# 4_F2838_JTAG_CLOCK_SUP.net
KiCad netlist of a schematic drawn in Altium Designer
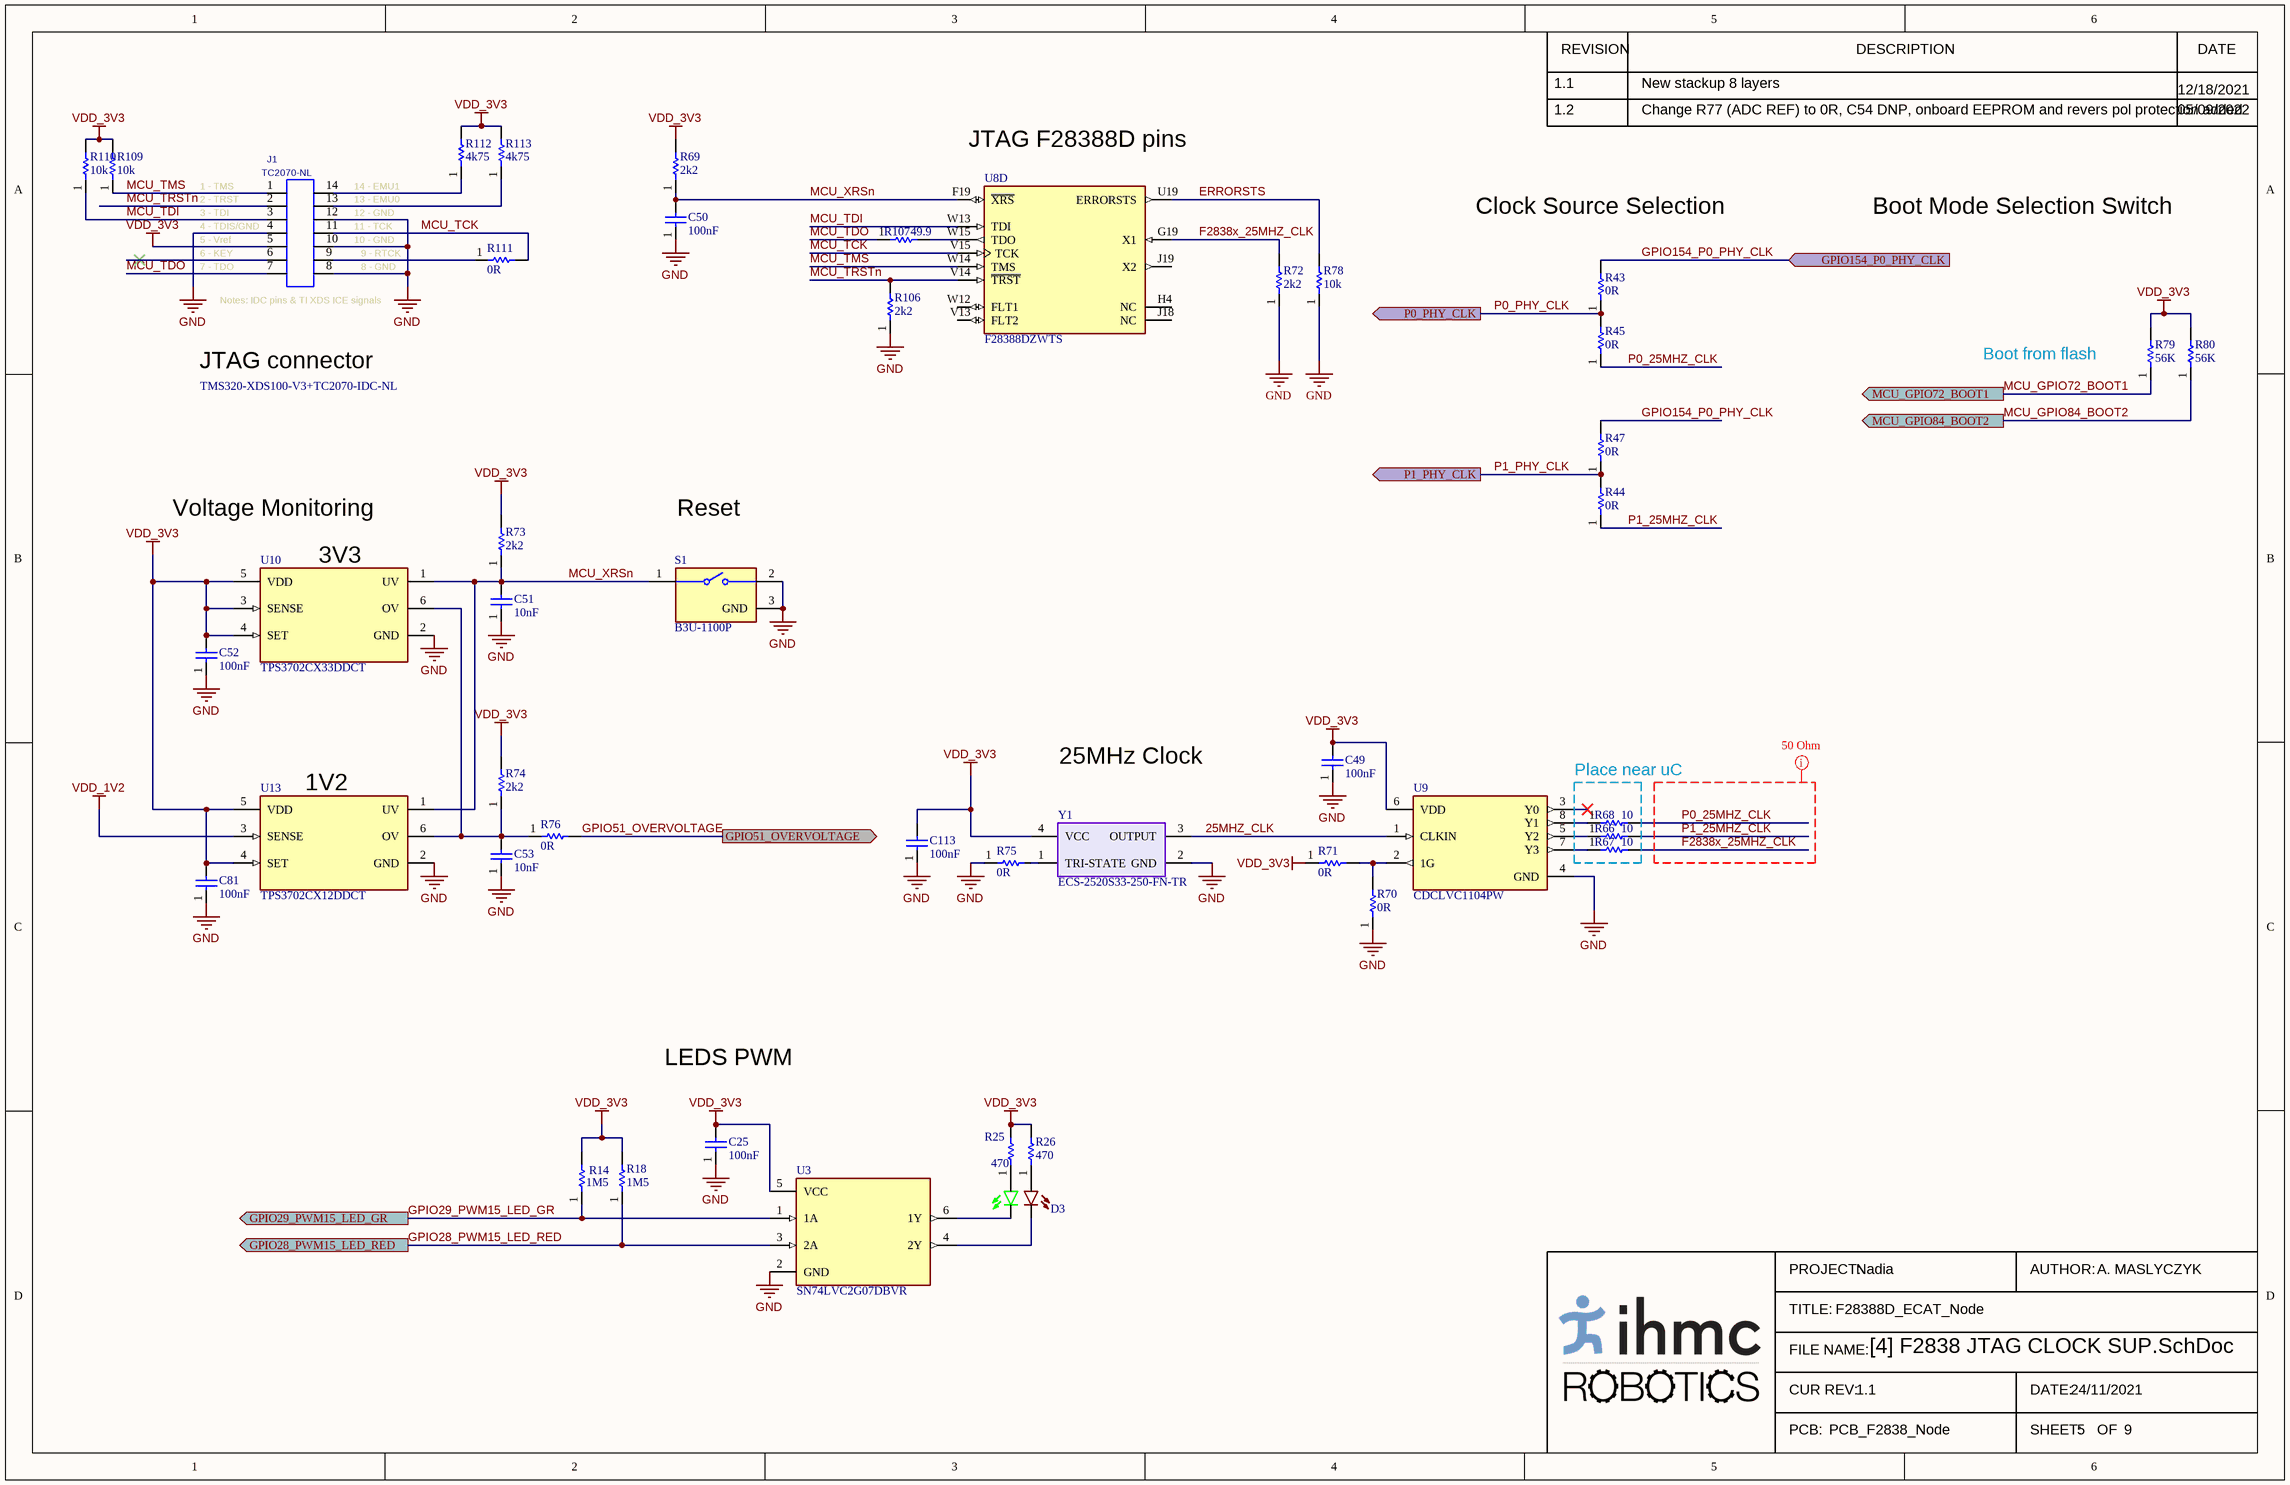
[diagram p0: [4] F2838 JTAG CLOCK SUP.SchDoc]

(export (version "E")
  (design (tool "Eeschema 10.0.6"))
  (components
    (comp (ref "C25")
      (value "100nF")
      (footprint "CAPC1005X03N(0402)")
      (description "CAP CER 0.1UF 16V X7R 0402")
      (fields (field (name "MPN") "GRM155R71C104JA88D") (field (name "TOLERANCE") "5%"))
      (libsource (lib "IHMC_Altium_Lib") (part "100nF_16V_0402_CAP"))
    )
    (comp (ref "C49")
      (value "100nF")
      (footprint "CAPC1005X03N(0402)")
      (description "CAP CER 0.1UF 16V X7R 0402")
      (fields (field (name "MPN") "GRM155R71C104JA88D") (field (name "TOLERANCE") "5%"))
      (libsource (lib "IHMC_Altium_Lib") (part "100nF_16V_0402_CAP"))
    )
    (comp (ref "C50")
      (value "100nF")
      (footprint "CAPC1005X03N(0402)")
      (description "CAP CER 0.1UF 16V X7R 0402")
      (fields (field (name "MPN") "GRM155R71C104JA88D") (field (name "TOLERANCE") "5%"))
      (libsource (lib "IHMC_Altium_Lib") (part "100nF_16V_0402_CAP"))
    )
    (comp (ref "C51")
      (value "10nF")
      (footprint "CAPC1005X03N(0402)")
      (description "CAP CER 10000PF 50V X7R 0402")
      (fields (field (name "MPN") "CC0402KRX7R9BB103") (field (name "VOLTAGE") "50V"))
      (libsource (lib "IHMC_Altium_Lib") (part "10nF_50V_0402_CAP"))
    )
    (comp (ref "C52")
      (value "100nF")
      (footprint "CAPC1005X03N(0402)")
      (description "CAP CER 0.1UF 16V X7R 0402")
      (fields (field (name "MPN") "GRM155R71C104JA88D") (field (name "TOLERANCE") "5%"))
      (libsource (lib "IHMC_Altium_Lib") (part "100nF_16V_0402_CAP"))
    )
    (comp (ref "C53")
      (value "10nF")
      (footprint "CAPC1005X03N(0402)")
      (description "CAP CER 10000PF 50V X7R 0402")
      (fields (field (name "MPN") "CC0402KRX7R9BB103") (field (name "VOLTAGE") "50V"))
      (libsource (lib "IHMC_Altium_Lib") (part "10nF_50V_0402_CAP"))
    )
    (comp (ref "C81")
      (value "100nF")
      (footprint "CAPC1608X09N(0603)")
      (description "CAP CER 0.1UF 50V X7R 0603")
      (fields (field (name "MPN") "CL10B104KB8NNNL") (field (name "TOLERANCE") "105"))
      (libsource (lib "IHMC_Altium_Lib") (part "100nF_50V_0603_CAP"))
    )
    (comp (ref "C113")
      (value "100nF")
      (footprint "CAPC1005X03N(0402)")
      (description "CAP CER 0.1UF 16V X7R 0402")
      (fields (field (name "MPN") "GRM155R71C104JA88D") (field (name "TOLERANCE") "5%"))
      (libsource (lib "IHMC_Altium_Lib") (part "100nF_16V_0402_CAP"))
    )
    (comp (ref "D3")
      (value "LTST-C195KGJRKT")
      (footprint "Dual_LED")
      (description "LED GREEN/RED CLEAR CHIP SMD")
      (libsource (lib "IHMC_Altium_Lib") (part "Green/Red_LED"))
    )
    (comp (ref "J1")
      (value "TC2070-NL")
      (footprint "TC2070-NL")
      (description "HDR, TC2070, 14 Pin, Footprint only")
      (libsource (lib "IHMC_Altium_Lib") (part "HDR 14 TC2070-NL"))
    )
    (comp (ref "R14")
      (value "1M5")
      (footprint "0402")
      (description "RES SMD 1.5M OHM 5% 1/16W 0402")
      (fields
        (field (name "MANUFACTURER") "Vishay Dale")
        (field (name "MANUFACTURER PART NUMBER") "CRCW04021M50JNED")
      )
      (libsource (lib "IHMC_Altium_Lib") (part "1M5_1/16W_0402_CRCW04021M50JNED_RES"))
    )
    (comp (ref "R18")
      (value "1M5")
      (footprint "0402")
      (description "RES SMD 1.5M OHM 5% 1/16W 0402")
      (fields
        (field (name "MANUFACTURER") "Vishay Dale")
        (field (name "MANUFACTURER PART NUMBER") "CRCW04021M50JNED")
      )
      (libsource (lib "IHMC_Altium_Lib") (part "1M5_1/16W_0402_CRCW04021M50JNED_RES"))
    )
    (comp (ref "R25")
      (value "470")
      (footprint "0402")
      (description "Vishay CRCW Series Thick Film Resistor 0402 Case 470 5% 0.063W 200ppm/K")
      (fields
        (field (name "MANUFACTURER") "Vishay Dale")
        (field (name "MANUFACTURER PART NUMBER") "CRCW0402470RJNED")
      )
      (libsource (lib "IHMC_Altium_Lib") (part "470_1/10W_0402_CRCW0402470RJNED"))
    )
    (comp (ref "R26")
      (value "470")
      (footprint "0402")
      (description "Vishay CRCW Series Thick Film Resistor 0402 Case 470 5% 0.063W 200ppm/K")
      (fields
        (field (name "MANUFACTURER") "Vishay Dale")
        (field (name "MANUFACTURER PART NUMBER") "CRCW0402470RJNED")
      )
      (libsource (lib "IHMC_Altium_Lib") (part "470_1/10W_0402_CRCW0402470RJNED"))
    )
    (comp (ref "R43")
      (value "0R")
      (footprint "0402")
      (fields
        (field (name "MANUFACTURER") "Vishay Dale")
        (field (name "MANUFACTURER PART NUMBER") "RCS04020000Z0ED")
      )
      (libsource (lib "IHMC_Altium_Lib") (part "0R_1/5W_0402_RCS04020000Z0ED_RES"))
    )
    (comp (ref "R44")
      (value "0R")
      (footprint "0402")
      (fields
        (field (name "MANUFACTURER") "Vishay Dale")
        (field (name "MANUFACTURER PART NUMBER") "RCS04020000Z0ED")
      )
      (libsource (lib "IHMC_Altium_Lib") (part "0R_1/5W_0402_RCS04020000Z0ED_RES"))
    )
    (comp (ref "R45")
      (value "0R")
      (footprint "0402")
      (fields
        (field (name "MANUFACTURER") "Vishay Dale")
        (field (name "MANUFACTURER PART NUMBER") "RCS04020000Z0ED")
      )
      (libsource (lib "IHMC_Altium_Lib") (part "0R_1/5W_0402_RCS04020000Z0ED_RES"))
    )
    (comp (ref "R47")
      (value "0R")
      (footprint "0402")
      (fields
        (field (name "MANUFACTURER") "Vishay Dale")
        (field (name "MANUFACTURER PART NUMBER") "RCS04020000Z0ED")
      )
      (libsource (lib "IHMC_Altium_Lib") (part "0R_1/5W_0402_RCS04020000Z0ED_RES"))
    )
    (comp (ref "R66")
      (value "10")
      (footprint "0402")
      (description "Res Thin Film 0402 10 Ohm 0.5% 1/16W 100ppm/C Molded SMD SMD Punched Carrier T/R")
      (fields
        (field (name "MANUFACTURER") "Panasonic")
        (field (name "MANUFACTURER PART NUMBER") "ERA-2AKD100X")
      )
      (libsource (lib "IHMC_Altium_Lib") (part "10R_0402_0.5%_ERA-2AKD100X"))
    )
    (comp (ref "R67")
      (value "10")
      (footprint "0402")
      (description "Res Thin Film 0402 10 Ohm 0.5% 1/16W 100ppm/C Molded SMD SMD Punched Carrier T/R")
      (fields
        (field (name "MANUFACTURER") "Panasonic")
        (field (name "MANUFACTURER PART NUMBER") "ERA-2AKD100X")
      )
      (libsource (lib "IHMC_Altium_Lib") (part "10R_0402_0.5%_ERA-2AKD100X"))
    )
    (comp (ref "R68")
      (value "10")
      (footprint "0402")
      (description "Res Thin Film 0402 10 Ohm 0.5% 1/16W 100ppm/C Molded SMD SMD Punched Carrier T/R")
      (fields
        (field (name "MANUFACTURER") "Panasonic")
        (field (name "MANUFACTURER PART NUMBER") "ERA-2AKD100X")
      )
      (libsource (lib "IHMC_Altium_Lib") (part "10R_0402_0.5%_ERA-2AKD100X"))
    )
    (comp (ref "R69")
      (value "2k2")
      (footprint "0402")
      (description "Vishay CRCW Series Thick Film Resistor 0402 Case 2.2k 5% 0.063W 200ppm/K")
      (fields
        (field (name "MANUFACTURER") "Vishay Dale")
        (field (name "MANUFACTURER PART NUMBER") "CRCW04022K20JNED")
      )
      (libsource (lib "IHMC_Altium_Lib") (part "2k2_1/16_0402_CRCW04022K20JNED_RES"))
    )
    (comp (ref "R70")
      (value "0R")
      (footprint "0402")
      (fields
        (field (name "MANUFACTURER") "Vishay Dale")
        (field (name "MANUFACTURER PART NUMBER") "RCS04020000Z0ED")
      )
      (libsource (lib "IHMC_Altium_Lib") (part "0R_1/5W_0402_RCS04020000Z0ED_RES"))
    )
    (comp (ref "R71")
      (value "0R")
      (footprint "0402")
      (fields
        (field (name "MANUFACTURER") "Vishay Dale")
        (field (name "MANUFACTURER PART NUMBER") "RCS04020000Z0ED")
      )
      (libsource (lib "IHMC_Altium_Lib") (part "0R_1/5W_0402_RCS04020000Z0ED_RES"))
    )
    (comp (ref "R72")
      (value "2k2")
      (footprint "0402")
      (description "Vishay CRCW Series Thick Film Resistor 0402 Case 2.2k 5% 0.063W 200ppm/K")
      (fields
        (field (name "MANUFACTURER") "Vishay Dale")
        (field (name "MANUFACTURER PART NUMBER") "CRCW04022K20JNED")
      )
      (libsource (lib "IHMC_Altium_Lib") (part "2k2_1/16_0402_CRCW04022K20JNED_RES"))
    )
    (comp (ref "R73")
      (value "2k2")
      (footprint "0402")
      (description "Vishay CRCW Series Thick Film Resistor 0402 Case 2.2k 5% 0.063W 200ppm/K")
      (fields
        (field (name "MANUFACTURER") "Vishay Dale")
        (field (name "MANUFACTURER PART NUMBER") "CRCW04022K20JNED")
      )
      (libsource (lib "IHMC_Altium_Lib") (part "2k2_1/16_0402_CRCW04022K20JNED_RES"))
    )
    (comp (ref "R74")
      (value "2k2")
      (footprint "0402")
      (description "Vishay CRCW Series Thick Film Resistor 0402 Case 2.2k 5% 0.063W 200ppm/K")
      (fields
        (field (name "MANUFACTURER") "Vishay Dale")
        (field (name "MANUFACTURER PART NUMBER") "CRCW04022K20JNED")
      )
      (libsource (lib "IHMC_Altium_Lib") (part "2k2_1/16_0402_CRCW04022K20JNED_RES"))
    )
    (comp (ref "R75")
      (value "0R")
      (footprint "0402")
      (fields
        (field (name "MANUFACTURER") "Vishay Dale")
        (field (name "MANUFACTURER PART NUMBER") "RCS04020000Z0ED")
      )
      (libsource (lib "IHMC_Altium_Lib") (part "0R_1/5W_0402_RCS04020000Z0ED_RES"))
    )
    (comp (ref "R76")
      (value "0R")
      (footprint "0402")
      (fields
        (field (name "MANUFACTURER") "Vishay Dale")
        (field (name "MANUFACTURER PART NUMBER") "RCS04020000Z0ED")
      )
      (libsource (lib "IHMC_Altium_Lib") (part "0R_1/5W_0402_RCS04020000Z0ED_RES"))
    )
    (comp (ref "R78")
      (value "10k")
      (footprint "RESC1005X06N(0402)")
      (description "RES SMD 10K OHM 1% 1/16W 0402")
      (fields (field (name "TOLERANCE") "1%") (field (name "POWER") "1/16W"))
      (libsource (lib "IHMC_Altium_Lib") (part "10k_1/16W_0402_RES"))
    )
    (comp (ref "R79")
      (value "56K")
      (footprint "0402")
      (description "Res Thick Film 0402 56K Ohm 5% 0.063W(1/16W) ±200ppm/C Pad SMD Automotive T/R")
      (fields
        (field (name "MANUFACTURER") "Vishay Dale")
        (field (name "MANUFACTURER PART NUMBER") "CRCW040256K0JNED")
      )
      (libsource (lib "IHMC_Altium_Lib") (part "56K_5%_0402_CRCW040256K0JNED_RES"))
    )
    (comp (ref "R80")
      (value "56K")
      (footprint "0402")
      (description "Res Thick Film 0402 56K Ohm 5% 0.063W(1/16W) ±200ppm/C Pad SMD Automotive T/R")
      (fields
        (field (name "MANUFACTURER") "Vishay Dale")
        (field (name "MANUFACTURER PART NUMBER") "CRCW040256K0JNED")
      )
      (libsource (lib "IHMC_Altium_Lib") (part "56K_5%_0402_CRCW040256K0JNED_RES"))
    )
    (comp (ref "R106")
      (value "2k2")
      (footprint "0402")
      (description "Vishay CRCW Series Thick Film Resistor 0402 Case 2.2k 5% 0.063W 200ppm/K")
      (fields
        (field (name "MANUFACTURER") "Vishay Dale")
        (field (name "MANUFACTURER PART NUMBER") "CRCW04022K20JNED")
      )
      (libsource (lib "IHMC_Altium_Lib") (part "2k2_1/16_0402_CRCW04022K20JNED_RES"))
    )
    (comp (ref "R107")
      (value "49.9")
      (footprint "RESC1005X06N(0402)")
      (description "RES SMD 49.9 OHM 1% 1/16W 0402")
      (fields
        (field (name "MPN") "CRCW040249R9FKED")
        (field (name "TOLERANCE") "1%")
        (field (name "DRAWN BY") "TC")
      )
      (libsource (lib "IHMC_Altium_Lib") (part "49R9_1/10W_0402_RES"))
    )
    (comp (ref "R109")
      (value "10k")
      (footprint "RESC1005X06N(0402)")
      (description "RES SMD 10K OHM 1% 1/16W 0402")
      (fields (field (name "TOLERANCE") "1%") (field (name "POWER") "1/16W"))
      (libsource (lib "IHMC_Altium_Lib") (part "10k_1/16W_0402_RES"))
    )
    (comp (ref "R110")
      (value "10k")
      (footprint "RESC1005X06N(0402)")
      (description "RES SMD 10K OHM 1% 1/16W 0402")
      (fields (field (name "TOLERANCE") "1%") (field (name "POWER") "1/16W"))
      (libsource (lib "IHMC_Altium_Lib") (part "10k_1/16W_0402_RES"))
    )
    (comp (ref "R111")
      (value "0R")
      (footprint "0402")
      (fields
        (field (name "MANUFACTURER") "Vishay Dale")
        (field (name "MANUFACTURER PART NUMBER") "RCS04020000Z0ED")
      )
      (libsource (lib "IHMC_Altium_Lib") (part "0R_1/5W_0402_RCS04020000Z0ED_RES"))
    )
    (comp (ref "R112")
      (value "4k75")
      (footprint "RESC1005X06N(0402)")
      (description "RES SMD 4.75K OHM 1% 1/16W 0402")
      (fields (field (name "MPN") "RC0402FR-074K75L") (field (name "POWER") "1/16"))
      (libsource (lib "IHMC_Altium_Lib") (part "4k75_1/16_0402_RES"))
    )
    (comp (ref "R113")
      (value "4k75")
      (footprint "RESC1005X06N(0402)")
      (description "RES SMD 4.75K OHM 1% 1/16W 0402")
      (fields (field (name "MPN") "RC0402FR-074K75L") (field (name "POWER") "1/16"))
      (libsource (lib "IHMC_Altium_Lib") (part "4k75_1/16_0402_RES"))
    )
    (comp (ref "S1")
      (value "B3U-1100P")
      (footprint "FP-B3U-1100P-MFSWITCH_G")
      (description "Switch Tactile N.O. SPST Round Button Gull Wing 0.05A 12VDC 1.5N SMD Embossed T/R")
      (fields (field (name "MANUFACTURER") "Omron"))
      (libsource (lib "IHMC_Altium_Lib") (part "SWITCH_SPST_NO_B3U-1100P"))
    )
    (comp (ref "U3")
      (value "SN74LVC2G07DBVR")
      (footprint "DBV0006A_M")
      (description "Buffer/Driver 2-CH Non-Inverting Open Drain CMOS 6-Pin SOT-23 T/R")
      (fields (field (name "MANUFACTURER") "Texas Instruments"))
      (libsource (lib "IHMC_Altium_Lib") (part "BUF_NONINV_SN74LVC2G07DBVR_SOT23"))
    )
    (comp (ref "U8")
      (value "F28388DZWTS")
      (footprint "FP-ZWT0337A-IPC_B - ESNACK")
      (fields
        (field (name "MANUFACTURER") "Texas instruments")
        (field (name "OCTOPART") "https://octopart.com/f28388dzwts-texas+instruments-102550657")
      )
      (libsource (lib "IHMC_IC") (part "TMS320F28388D_32bit_uC"))
    )
    (comp (ref "U9")
      (value "CDCLVC1104PW")
      (footprint "FP-PW0008A-IPC_C-FIXONSHAPE")
      (description "Clock Fanout Buffer 4-OUT 8-Pin TSSOP Tube")
      (fields (field (name "MANUFACTURER") "Texas Instruments"))
      (libsource (lib "IHMC_IC") (part "BUF_CLOCK_CDCLVC1104PW"))
    )
    (comp (ref "U10")
      (value "TPS3702CX33DDCT")
      (footprint "FP-DDC0006A-IPC_A")
      (description "Processor Supervisor 3.3V 1 Active Low/Open Drain 6-Pin TSOT-23 T/R")
      (fields (field (name "MANUFACTURER") "Texas Instruments"))
      (libsource (lib "IHMC_IC") (part "SUPERVISOR_3V3_TPS3702CX33DDCT_TSOT"))
    )
    (comp (ref "U13")
      (value "TPS3702CX12DDCT")
      (footprint "FP-DDC0006A-IPC_A")
      (description "Processor Supervisor 1.2V 1 Active Low/Open Drain 6-Pin TSOT-23 T/R")
      (fields (field (name "MANUFACTURER") "Texas Instruments"))
      (libsource (lib "IHMC_IC") (part "SUPERVISOR_1V2_TPS3702CX12DDCT_TSOT"))
    )
    (comp (ref "Y1")
      (value "ECS-2520S33-250-FN-TR")
      (footprint "XTAL_ECS-2520S")
      (description "Oscillator XO 25MHz ±10ppm 15pF HCMOS 55% 3.3V 4-Pin Mini-CSMD T/R")
      (fields (field (name "MANUFACTURER") "ECS International"))
      (libsource (lib "IHMC_Altium_Lib") (part "25MHz_XTAL_ECS-2520S33-250-FN-TR"))
    )
  )
  (nets
    (net (code "1") (name "/25MHZ_CLK") (class "Default")
      (node (ref "U9") (pin "1") (pinfunction "CLKIN_1") (pintype "input"))
      (node (ref "Y1") (pin "3") (pinfunction "OUTPUT_3") (pintype "passive"))
    )
    (net (code "2") (name "/ERRORSTS") (class "Default")
      (node (ref "R78") (pin "2") (pinfunction "2_2") (pintype "passive"))
      (node (ref "U8") (pin "U19") (pinfunction "ERRORSTS_U19") (pintype "output"))
    )
    (net (code "3") (name "/F2838x_25MHZ_CLK") (class "Default")
      (node (ref "R67") (pin "2") (pinfunction "2_2") (pintype "passive"))
      (node (ref "R72") (pin "2") (pinfunction "2_2") (pintype "passive"))
      (node (ref "U8") (pin "G19") (pinfunction "X1_G19") (pintype "input"))
    )
    (net (code "4") (name "/GPIO28_PWM15_LED_RED") (class "Default")
      (node (ref "R18") (pin "1") (pinfunction "1_1") (pintype "passive"))
      (node (ref "U3") (pin "3") (pinfunction "2A_3") (pintype "input"))
    )
    (net (code "5") (name "/GPIO29_PWM15_LED_GR") (class "Default")
      (node (ref "R14") (pin "1") (pinfunction "1_1") (pintype "passive"))
      (node (ref "U3") (pin "1") (pinfunction "1A_1") (pintype "input"))
    )
    (net (code "6") (name "/GPIO51_OVERVOLTAGE") (class "Default")
      (node (ref "R76") (pin "2") (pinfunction "2_2") (pintype "passive"))
    )
    (net (code "7") (name "/GPIO154_P0_PHY_CLK") (class "Default")
      (node (ref "R43") (pin "2") (pinfunction "2_2") (pintype "passive"))
      (node (ref "R47") (pin "2") (pinfunction "2_2") (pintype "passive"))
    )
    (net (code "8") (name "/MCU_GPIO72_BOOT1") (class "Default")
      (node (ref "R79") (pin "1") (pinfunction "1_1") (pintype "passive"))
    )
    (net (code "9") (name "/MCU_GPIO84_BOOT2") (class "Default")
      (node (ref "R80") (pin "1") (pinfunction "1_1") (pintype "passive"))
    )
    (net (code "10") (name "/MCU_TCK") (class "Default")
      (node (ref "J1") (pin "11") (pinfunction "11_11") (pintype "passive"))
      (node (ref "R111") (pin "2") (pinfunction "2_2") (pintype "passive"))
      (node (ref "U8") (pin "V15") (pinfunction "TCK_V15") (pintype "input"))
    )
    (net (code "11") (name "/MCU_TDI") (class "Default")
      (node (ref "J1") (pin "3") (pinfunction "3_3") (pintype "passive"))
      (node (ref "R110") (pin "1") (pinfunction "1_1") (pintype "passive"))
      (node (ref "U8") (pin "W13") (pinfunction "TDI_W13") (pintype "input"))
    )
    (net (code "12") (name "/MCU_TDO") (class "Default")
      (node (ref "J1") (pin "7") (pinfunction "7_7") (pintype "passive"))
      (node (ref "R107") (pin "1") (pinfunction "1_1") (pintype "passive"))
    )
    (net (code "13") (name "/MCU_TMS") (class "Default")
      (node (ref "J1") (pin "1") (pinfunction "1_1") (pintype "passive"))
      (node (ref "R109") (pin "1") (pinfunction "1_1") (pintype "passive"))
      (node (ref "U8") (pin "W14") (pinfunction "TMS_W14") (pintype "input"))
    )
    (net (code "14") (name "/MCU_TRSTn") (class "Default")
      (node (ref "J1") (pin "2") (pinfunction "2_2") (pintype "passive"))
      (node (ref "R106") (pin "2") (pinfunction "2_2") (pintype "passive"))
      (node (ref "U8") (pin "V14") (pinfunction "~{TRST}_V14") (pintype "input"))
    )
    (net (code "15") (name "/MCU_XRSn") (class "Default")
      (node (ref "C50") (pin "2") (pinfunction "2_2") (pintype "passive"))
      (node (ref "C51") (pin "2") (pinfunction "2_2") (pintype "passive"))
      (node (ref "R69") (pin "1") (pinfunction "1_1") (pintype "passive"))
      (node (ref "R73") (pin "1") (pinfunction "1_1") (pintype "passive"))
      (node (ref "S1") (pin "1") (pinfunction "1_1") (pintype "passive"))
      (node (ref "U10") (pin "1") (pinfunction "UV_1") (pintype "passive"))
      (node (ref "U13") (pin "1") (pinfunction "UV_1") (pintype "passive"))
      (node (ref "U8") (pin "F19") (pinfunction "~{XRS}_F19") (pintype "bidirectional"))
    )
    (net (code "16") (name "/P0_25MHZ_CLK") (class "Default")
      (node (ref "R45") (pin "1") (pinfunction "1_1") (pintype "passive"))
      (node (ref "R68") (pin "2") (pinfunction "2_2") (pintype "passive"))
    )
    (net (code "17") (name "/P0_PHY_CLK") (class "Default")
      (node (ref "R43") (pin "1") (pinfunction "1_1") (pintype "passive"))
      (node (ref "R45") (pin "2") (pinfunction "2_2") (pintype "passive"))
    )
    (net (code "18") (name "/P1_25MHZ_CLK") (class "Default")
      (node (ref "R44") (pin "1") (pinfunction "1_1") (pintype "passive"))
      (node (ref "R66") (pin "2") (pinfunction "2_2") (pintype "passive"))
    )
    (net (code "19") (name "/P1_PHY_CLK") (class "Default")
      (node (ref "R44") (pin "2") (pinfunction "2_2") (pintype "passive"))
      (node (ref "R47") (pin "1") (pinfunction "1_1") (pintype "passive"))
    )
    (net (code "20") (name "GND") (class "Default")
      (node (ref "C113") (pin "1") (pinfunction "1_1") (pintype "passive"))
      (node (ref "C25") (pin "1") (pinfunction "1_1") (pintype "passive"))
      (node (ref "C49") (pin "1") (pinfunction "1_1") (pintype "passive"))
      (node (ref "C50") (pin "1") (pinfunction "1_1") (pintype "passive"))
      (node (ref "C51") (pin "1") (pinfunction "1_1") (pintype "passive"))
      (node (ref "C52") (pin "1") (pinfunction "1_1") (pintype "passive"))
      (node (ref "C53") (pin "1") (pinfunction "1_1") (pintype "passive"))
      (node (ref "C81") (pin "1") (pinfunction "1_1") (pintype "passive"))
      (node (ref "J1") (pin "10") (pinfunction "10_10") (pintype "passive"))
      (node (ref "J1") (pin "12") (pinfunction "12_12") (pintype "passive"))
      (node (ref "J1") (pin "4") (pinfunction "4_4") (pintype "passive"))
      (node (ref "J1") (pin "8") (pinfunction "8_8") (pintype "passive"))
      (node (ref "R106") (pin "1") (pinfunction "1_1") (pintype "passive"))
      (node (ref "R70") (pin "1") (pinfunction "1_1") (pintype "passive"))
      (node (ref "R72") (pin "1") (pinfunction "1_1") (pintype "passive"))
      (node (ref "R75") (pin "1") (pinfunction "1_1") (pintype "passive"))
      (node (ref "R78") (pin "1") (pinfunction "1_1") (pintype "passive"))
      (node (ref "S1") (pin "2") (pinfunction "2_2") (pintype "passive"))
      (node (ref "S1") (pin "3") (pinfunction "GND_3") (pintype "power_in"))
      (node (ref "U10") (pin "2") (pinfunction "GND_2") (pintype "power_in"))
      (node (ref "U13") (pin "2") (pinfunction "GND_2") (pintype "power_in"))
      (node (ref "U3") (pin "2") (pinfunction "GND_2") (pintype "power_in"))
      (node (ref "U9") (pin "4") (pinfunction "GND_4") (pintype "power_in"))
      (node (ref "Y1") (pin "2") (pinfunction "GND_2") (pintype "passive"))
    )
    (net (code "21") (name "Net-(D3-Pad1)") (class "Default")
      (node (ref "D3") (pin "1") (pinfunction "1_1") (pintype "passive"))
      (node (ref "R25") (pin "1") (pinfunction "1_1") (pintype "passive"))
    )
    (net (code "22") (name "Net-(D3-Pad2)") (class "Default")
      (node (ref "D3") (pin "2") (pinfunction "2_2") (pintype "passive"))
      (node (ref "R26") (pin "1") (pinfunction "1_1") (pintype "passive"))
    )
    (net (code "23") (name "Net-(J1-Pad9)") (class "Default")
      (node (ref "J1") (pin "9") (pinfunction "9_9") (pintype "passive"))
      (node (ref "R111") (pin "1") (pinfunction "1_1") (pintype "passive"))
    )
    (net (code "24") (name "Net-(J1-Pad13)") (class "Default")
      (node (ref "J1") (pin "13") (pinfunction "13_13") (pintype "passive"))
      (node (ref "R113") (pin "1") (pinfunction "1_1") (pintype "passive"))
    )
    (net (code "25") (name "Net-(J1-Pad14)") (class "Default")
      (node (ref "J1") (pin "14") (pinfunction "14_14") (pintype "passive"))
      (node (ref "R112") (pin "1") (pinfunction "1_1") (pintype "passive"))
    )
    (net (code "26") (name "Net-(U3-1Y)") (class "Default")
      (node (ref "D3") (pin "3") (pinfunction "3_3") (pintype "passive"))
      (node (ref "U3") (pin "6") (pinfunction "1Y_6") (pintype "output"))
    )
    (net (code "27") (name "Net-(U3-2Y)") (class "Default")
      (node (ref "D3") (pin "4") (pinfunction "4_4") (pintype "passive"))
      (node (ref "U3") (pin "4") (pinfunction "2Y_4") (pintype "output"))
    )
    (net (code "28") (name "Net-(U8D-TDO)") (class "Default")
      (node (ref "R107") (pin "2") (pinfunction "2_2") (pintype "passive"))
      (node (ref "U8") (pin "W15") (pinfunction "TDO_W15") (pintype "output"))
    )
    (net (code "29") (name "Net-(U9-1G)") (class "Default")
      (node (ref "R70") (pin "2") (pinfunction "2_2") (pintype "passive"))
      (node (ref "R71") (pin "2") (pinfunction "2_2") (pintype "passive"))
      (node (ref "U9") (pin "2") (pinfunction "1G_2") (pintype "output"))
    )
    (net (code "30") (name "Net-(U9-Y1)") (class "Default")
      (node (ref "R68") (pin "1") (pinfunction "1_1") (pintype "passive"))
      (node (ref "U9") (pin "8") (pinfunction "Y1_8") (pintype "output"))
    )
    (net (code "31") (name "Net-(U9-Y2)") (class "Default")
      (node (ref "R66") (pin "1") (pinfunction "1_1") (pintype "passive"))
      (node (ref "U9") (pin "5") (pinfunction "Y2_5") (pintype "output"))
    )
    (net (code "32") (name "Net-(U9-Y3)") (class "Default")
      (node (ref "R67") (pin "1") (pinfunction "1_1") (pintype "passive"))
      (node (ref "U9") (pin "7") (pinfunction "Y3_7") (pintype "output"))
    )
    (net (code "33") (name "Net-(U10-OV)") (class "Default")
      (node (ref "C53") (pin "2") (pinfunction "2_2") (pintype "passive"))
      (node (ref "R74") (pin "1") (pinfunction "1_1") (pintype "passive"))
      (node (ref "R76") (pin "1") (pinfunction "1_1") (pintype "passive"))
      (node (ref "U10") (pin "6") (pinfunction "OV_6") (pintype "passive"))
      (node (ref "U13") (pin "6") (pinfunction "OV_6") (pintype "passive"))
    )
    (net (code "34") (name "Net-(Y1-TRI-STATE)") (class "Default")
      (node (ref "R75") (pin "2") (pinfunction "2_2") (pintype "passive"))
      (node (ref "Y1") (pin "1") (pinfunction "TRI-STATE_1") (pintype "passive"))
    )
    (net (code "35") (name "VDD_1V2") (class "Default")
      (node (ref "U13") (pin "3") (pinfunction "SENSE_3") (pintype "input"))
    )
    (net (code "36") (name "VDD_3V3") (class "Default")
      (node (ref "C113") (pin "2") (pinfunction "2_2") (pintype "passive"))
      (node (ref "C25") (pin "2") (pinfunction "2_2") (pintype "passive"))
      (node (ref "C49") (pin "2") (pinfunction "2_2") (pintype "passive"))
      (node (ref "C52") (pin "2") (pinfunction "2_2") (pintype "passive"))
      (node (ref "C81") (pin "2") (pinfunction "2_2") (pintype "passive"))
      (node (ref "J1") (pin "5") (pinfunction "5_5") (pintype "passive"))
      (node (ref "R109") (pin "2") (pinfunction "2_2") (pintype "passive"))
      (node (ref "R110") (pin "2") (pinfunction "2_2") (pintype "passive"))
      (node (ref "R112") (pin "2") (pinfunction "2_2") (pintype "passive"))
      (node (ref "R113") (pin "2") (pinfunction "2_2") (pintype "passive"))
      (node (ref "R14") (pin "2") (pinfunction "2_2") (pintype "passive"))
      (node (ref "R18") (pin "2") (pinfunction "2_2") (pintype "passive"))
      (node (ref "R25") (pin "2") (pinfunction "2_2") (pintype "passive"))
      (node (ref "R26") (pin "2") (pinfunction "2_2") (pintype "passive"))
      (node (ref "R69") (pin "2") (pinfunction "2_2") (pintype "passive"))
      (node (ref "R71") (pin "1") (pinfunction "1_1") (pintype "passive"))
      (node (ref "R73") (pin "2") (pinfunction "2_2") (pintype "passive"))
      (node (ref "R74") (pin "2") (pinfunction "2_2") (pintype "passive"))
      (node (ref "R79") (pin "2") (pinfunction "2_2") (pintype "passive"))
      (node (ref "R80") (pin "2") (pinfunction "2_2") (pintype "passive"))
      (node (ref "U10") (pin "3") (pinfunction "SENSE_3") (pintype "input"))
      (node (ref "U10") (pin "4") (pinfunction "SET_4") (pintype "input"))
      (node (ref "U10") (pin "5") (pinfunction "VDD_5") (pintype "power_in"))
      (node (ref "U13") (pin "4") (pinfunction "SET_4") (pintype "input"))
      (node (ref "U13") (pin "5") (pinfunction "VDD_5") (pintype "power_in"))
      (node (ref "U3") (pin "5") (pinfunction "VCC_5") (pintype "power_in"))
      (node (ref "U9") (pin "6") (pinfunction "VDD_6") (pintype "power_in"))
      (node (ref "Y1") (pin "4") (pinfunction "VCC_4") (pintype "passive"))
    )
    (net (code "37") (name "unconnected-(J1-Pad6)") (class "Default")
      (node (ref "J1") (pin "6") (pinfunction "6_6") (pintype "passive"))
    )
    (net (code "38") (name "unconnected-(U8D-FLT1-PadW12)") (class "Default")
      (node (ref "U8") (pin "W12") (pinfunction "FLT1_W12") (pintype "bidirectional"))
    )
    (net (code "39") (name "unconnected-(U8D-FLT2-PadV13)") (class "Default")
      (node (ref "U8") (pin "V13") (pinfunction "FLT2_V13") (pintype "bidirectional"))
    )
    (net (code "40") (name "unconnected-(U8D-NC-PadH4)") (class "Default")
      (node (ref "U8") (pin "H4") (pinfunction "NC_H4") (pintype "passive"))
    )
    (net (code "41") (name "unconnected-(U8D-NC-PadJ18)") (class "Default")
      (node (ref "U8") (pin "J18") (pinfunction "NC_J18") (pintype "passive"))
    )
    (net (code "42") (name "unconnected-(U8D-X2-PadJ19)") (class "Default")
      (node (ref "U8") (pin "J19") (pinfunction "X2_J19") (pintype "output"))
    )
    (net (code "43") (name "unconnected-(U9-Y0-Pad3)") (class "Default")
      (node (ref "U9") (pin "3") (pinfunction "Y0_3") (pintype "output+no_connect"))
    )
  )
)
